# Main.net
KiCad netlist of a schematic drawn in Altium Designer
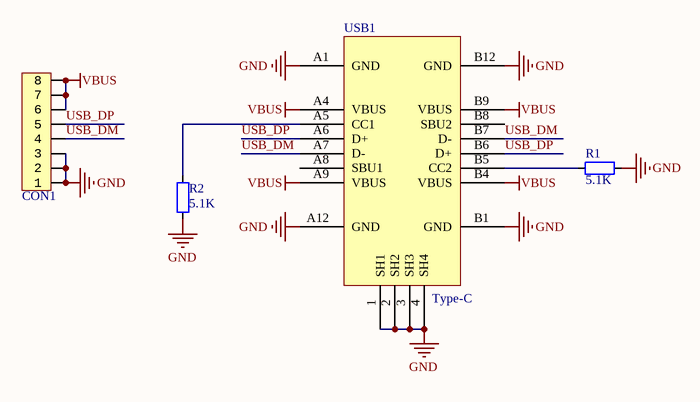
[diagram p0: Main.SchDoc]

(export (version "E")
  (design (tool "Eeschema 10.0.6"))
  (components
    (comp (ref "CON1")
      (value "FFC_0.5_8")
      (footprint "FFC_0.5_8")
      (description "FFC")
      (libsource (lib "KitSprout") (part "FFC_0.5_8"))
    )
    (comp (ref "R1")
      (value "5.1K")
      (footprint "RES_0402")
      (description "Resistor")
      (libsource (lib "MyPcbLib") (part "电阻-0402"))
    )
    (comp (ref "R2")
      (value "5.1K")
      (footprint "RES_0402")
      (description "Resistor")
      (libsource (lib "") (part "电阻-0402_1"))
    )
    (comp (ref "USB1")
      (value "Type-C")
      (footprint "Type-C-TOP")
      (libsource (lib "MyPcbLib") (part "USB-Type-C-TOP"))
    )
  )
  (nets
    (net (code "1") (name "/USB_DM") (class "Default")
      (node (ref "CON1") (pin "4") (pinfunction "4_4") (pintype "passive"))
      (node (ref "USB1") (pin "A7") (pinfunction "D-_A7") (pintype "passive"))
      (node (ref "USB1") (pin "B7") (pinfunction "D-_B7") (pintype "passive"))
    )
    (net (code "2") (name "/USB_DP") (class "Default")
      (node (ref "CON1") (pin "5") (pinfunction "5_5") (pintype "passive"))
      (node (ref "USB1") (pin "A6") (pinfunction "D+_A6") (pintype "passive"))
      (node (ref "USB1") (pin "B6") (pinfunction "D+_B6") (pintype "passive"))
    )
    (net (code "3") (name "GND") (class "Default")
      (node (ref "CON1") (pin "1") (pinfunction "1_1") (pintype "passive"))
      (node (ref "CON1") (pin "2") (pinfunction "2_2") (pintype "passive"))
      (node (ref "CON1") (pin "3") (pinfunction "3_3") (pintype "passive"))
      (node (ref "R1") (pin "1") (pinfunction "1_1") (pintype "passive"))
      (node (ref "R2") (pin "2") (pinfunction "2_2") (pintype "passive"))
      (node (ref "USB1") (pin "1") (pinfunction "SH1_1") (pintype "passive"))
      (node (ref "USB1") (pin "2") (pinfunction "SH2_2") (pintype "passive"))
      (node (ref "USB1") (pin "3") (pinfunction "SH3_3") (pintype "passive"))
      (node (ref "USB1") (pin "4") (pinfunction "SH4_4") (pintype "passive"))
      (node (ref "USB1") (pin "A1") (pinfunction "GND_A1") (pintype "passive"))
      (node (ref "USB1") (pin "A12") (pinfunction "GND_A12") (pintype "passive"))
      (node (ref "USB1") (pin "B1") (pinfunction "GND_B1") (pintype "passive"))
      (node (ref "USB1") (pin "B12") (pinfunction "GND_B12") (pintype "passive"))
    )
    (net (code "4") (name "Net-(USB1-CC1)") (class "Default")
      (node (ref "R2") (pin "1") (pinfunction "1_1") (pintype "passive"))
      (node (ref "USB1") (pin "A5") (pinfunction "CC1_A5") (pintype "passive"))
    )
    (net (code "5") (name "Net-(USB1-CC2)") (class "Default")
      (node (ref "R1") (pin "2") (pinfunction "2_2") (pintype "passive"))
      (node (ref "USB1") (pin "B5") (pinfunction "CC2_B5") (pintype "passive"))
    )
    (net (code "6") (name "VBUS") (class "Default")
      (node (ref "CON1") (pin "6") (pinfunction "6_6") (pintype "passive"))
      (node (ref "CON1") (pin "7") (pinfunction "7_7") (pintype "passive"))
      (node (ref "CON1") (pin "8") (pinfunction "8_8") (pintype "passive"))
      (node (ref "USB1") (pin "A4") (pinfunction "VBUS_A4") (pintype "passive"))
      (node (ref "USB1") (pin "A9") (pinfunction "VBUS_A9") (pintype "passive"))
      (node (ref "USB1") (pin "B4") (pinfunction "VBUS_B4") (pintype "passive"))
      (node (ref "USB1") (pin "B9") (pinfunction "VBUS_B9") (pintype "passive"))
    )
    (net (code "7") (name "unconnected-(USB1-SBU1-PadA8)") (class "Default")
      (node (ref "USB1") (pin "A8") (pinfunction "SBU1_A8") (pintype "passive"))
    )
    (net (code "8") (name "unconnected-(USB1-SBU2-PadB8)") (class "Default")
      (node (ref "USB1") (pin "B8") (pinfunction "SBU2_B8") (pintype "passive"))
    )
  )
)
